# ATtiny1634.net
KiCad netlist of a schematic drawn in EAGLE
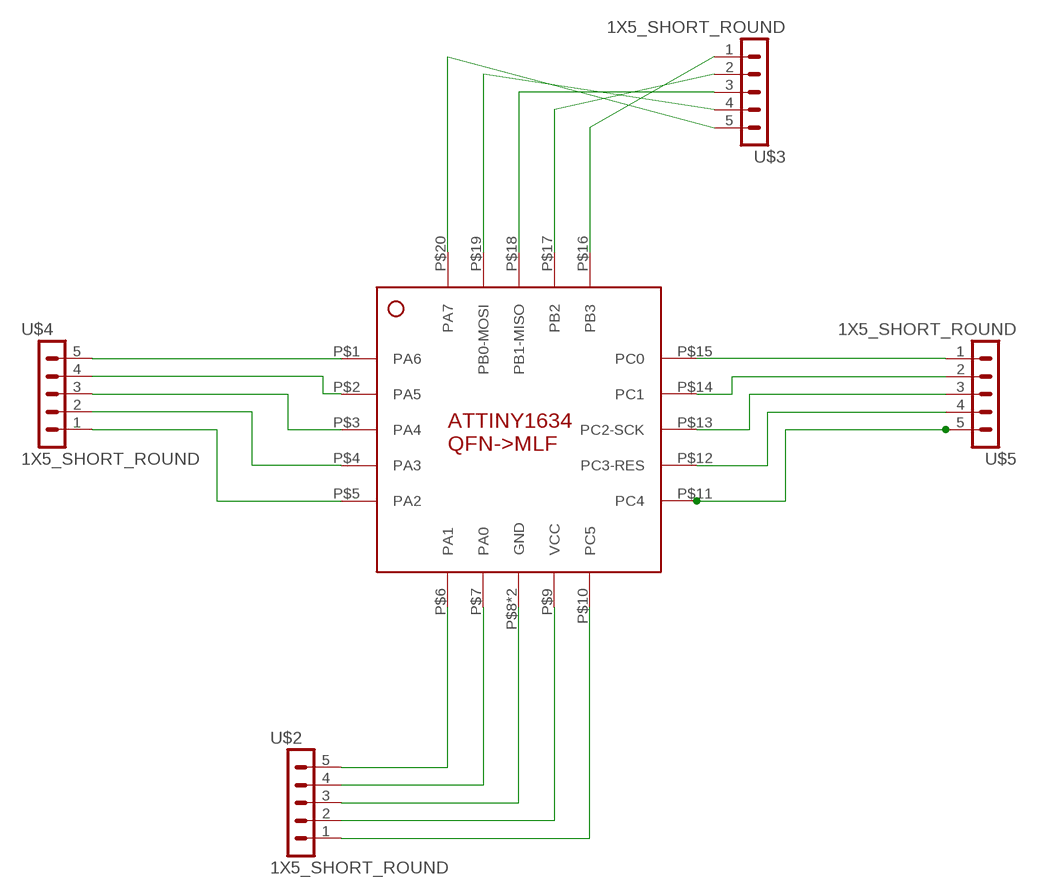
[diagram p0: schematic, sheet 1]

(export (version "E")
  (design (tool "Eeschema 10.0.6"))
  (components
    (comp (ref "U$1")
      (value "ATTINY1634")
      (footprint "eagle-import:MLF20_ATTINY13")
      (libsource (lib "eagle-import") (part "ATTINY1634"))
    )
    (comp (ref "U$2")
      (value "1X5_SHORT_ROUND")
      (footprint "eagle-import:1X5_SHORT_ROUND")
      (libsource (lib "eagle-import") (part "1X5_SHORT_ROUND"))
    )
    (comp (ref "U$3")
      (value "1X5_SHORT_ROUND")
      (footprint "eagle-import:1X5_SHORT_ROUND")
      (libsource (lib "eagle-import") (part "1X5_SHORT_ROUND"))
    )
    (comp (ref "U$4")
      (value "1X5_SHORT_ROUND")
      (footprint "eagle-import:1X5_SHORT_ROUND")
      (libsource (lib "eagle-import") (part "1X5_SHORT_ROUND"))
    )
    (comp (ref "U$5")
      (value "1X5_SHORT_ROUND")
      (footprint "eagle-import:1X5_SHORT_ROUND")
      (libsource (lib "eagle-import") (part "1X5_SHORT_ROUND"))
    )
  )
  (nets
    (net (code "1") (name "Net-(U$1-PA0)") (class "Default")
      (node (ref "U$1") (pin "P$7") (pinfunction "PA0_P$7") (pintype "bidirectional"))
      (node (ref "U$2") (pin "4") (pinfunction "5_4") (pintype "passive"))
    )
    (net (code "2") (name "Net-(U$1-PA1)") (class "Default")
      (node (ref "U$1") (pin "P$6") (pinfunction "PA1_P$6") (pintype "bidirectional"))
      (node (ref "U$2") (pin "5") (pinfunction "6_5") (pintype "passive"))
    )
    (net (code "3") (name "Net-(U$1-PA2)") (class "Default")
      (node (ref "U$1") (pin "P$5") (pinfunction "PA2_P$5") (pintype "bidirectional"))
      (node (ref "U$4") (pin "1") (pinfunction "2_1") (pintype "passive"))
    )
    (net (code "4") (name "Net-(U$1-PA3)") (class "Default")
      (node (ref "U$1") (pin "P$4") (pinfunction "PA3_P$4") (pintype "bidirectional"))
      (node (ref "U$4") (pin "2") (pinfunction "3_2") (pintype "passive"))
    )
    (net (code "5") (name "Net-(U$1-PA4)") (class "Default")
      (node (ref "U$1") (pin "P$3") (pinfunction "PA4_P$3") (pintype "bidirectional"))
      (node (ref "U$4") (pin "3") (pinfunction "4_3") (pintype "passive"))
    )
    (net (code "6") (name "Net-(U$1-PA5)") (class "Default")
      (node (ref "U$1") (pin "P$2") (pinfunction "PA5_P$2") (pintype "bidirectional"))
      (node (ref "U$4") (pin "4") (pinfunction "5_4") (pintype "passive"))
    )
    (net (code "7") (name "Net-(U$1-PA6)") (class "Default")
      (node (ref "U$1") (pin "P$1") (pinfunction "PA6_P$1") (pintype "bidirectional"))
      (node (ref "U$4") (pin "5") (pinfunction "6_5") (pintype "passive"))
    )
    (net (code "8") (name "Net-(U$1-PA7)") (class "Default")
      (node (ref "U$1") (pin "P$20") (pinfunction "PA7_P$20") (pintype "bidirectional"))
      (node (ref "U$3") (pin "5") (pinfunction "6_5") (pintype "passive"))
    )
    (net (code "9") (name "Net-(U$1-PB0-MOSI)") (class "Default")
      (node (ref "U$1") (pin "P$19") (pinfunction "PB0-MOSI_P$19") (pintype "bidirectional"))
      (node (ref "U$3") (pin "4") (pinfunction "5_4") (pintype "passive"))
    )
    (net (code "10") (name "Net-(U$1-PB1-MISO)") (class "Default")
      (node (ref "U$1") (pin "P$18") (pinfunction "PB1-MISO_P$18") (pintype "bidirectional"))
      (node (ref "U$3") (pin "3") (pinfunction "4_3") (pintype "passive"))
    )
    (net (code "11") (name "Net-(U$1-PB2)") (class "Default")
      (node (ref "U$1") (pin "P$17") (pinfunction "PB2_P$17") (pintype "bidirectional"))
      (node (ref "U$3") (pin "2") (pinfunction "3_2") (pintype "passive"))
    )
    (net (code "12") (name "Net-(U$1-PB3)") (class "Default")
      (node (ref "U$1") (pin "P$16") (pinfunction "PB3_P$16") (pintype "bidirectional"))
      (node (ref "U$3") (pin "1") (pinfunction "2_1") (pintype "passive"))
    )
    (net (code "13") (name "Net-(U$1-PC0)") (class "Default")
      (node (ref "U$1") (pin "P$15") (pinfunction "PC0_P$15") (pintype "bidirectional"))
      (node (ref "U$5") (pin "1") (pinfunction "2_1") (pintype "passive"))
    )
    (net (code "14") (name "Net-(U$1-PC1)") (class "Default")
      (node (ref "U$1") (pin "P$14") (pinfunction "PC1_P$14") (pintype "bidirectional"))
      (node (ref "U$5") (pin "2") (pinfunction "3_2") (pintype "passive"))
    )
    (net (code "15") (name "Net-(U$1-PC2-SCK)") (class "Default")
      (node (ref "U$1") (pin "P$13") (pinfunction "PC2-SCK_P$13") (pintype "bidirectional"))
      (node (ref "U$5") (pin "3") (pinfunction "4_3") (pintype "passive"))
    )
    (net (code "16") (name "Net-(U$1-PC3-RES)") (class "Default")
      (node (ref "U$1") (pin "P$12") (pinfunction "PC3-RES_P$12") (pintype "bidirectional"))
      (node (ref "U$5") (pin "4") (pinfunction "5_4") (pintype "passive"))
    )
    (net (code "17") (name "Net-(U$1-PC4)") (class "Default")
      (node (ref "U$1") (pin "P$11") (pinfunction "PC4_P$11") (pintype "bidirectional"))
      (node (ref "U$5") (pin "5") (pinfunction "6_5") (pintype "passive"))
    )
    (net (code "18") (name "Net-(U$1-PC5)") (class "Default")
      (node (ref "U$1") (pin "P$10") (pinfunction "PC5_P$10") (pintype "bidirectional"))
      (node (ref "U$2") (pin "1") (pinfunction "2_1") (pintype "passive"))
    )
    (net (code "19") (name "Net-(U$1-VCC)") (class "Default")
      (node (ref "U$1") (pin "P$9") (pinfunction "VCC_P$9") (pintype "bidirectional"))
      (node (ref "U$2") (pin "2") (pinfunction "3_2") (pintype "passive"))
    )
    (net (code "20") (name "Net-(U$2-4)") (class "Default")
      (node (ref "U$1") (pin "P$21") (pinfunction "GND_P$21") (pintype "bidirectional"))
      (node (ref "U$1") (pin "P$8") (pinfunction "GND_P$8") (pintype "bidirectional"))
      (node (ref "U$2") (pin "3") (pinfunction "4_3") (pintype "passive"))
    )
  )
)
